# sch_Power.net
KiCad netlist of a schematic drawn in Altium Designer
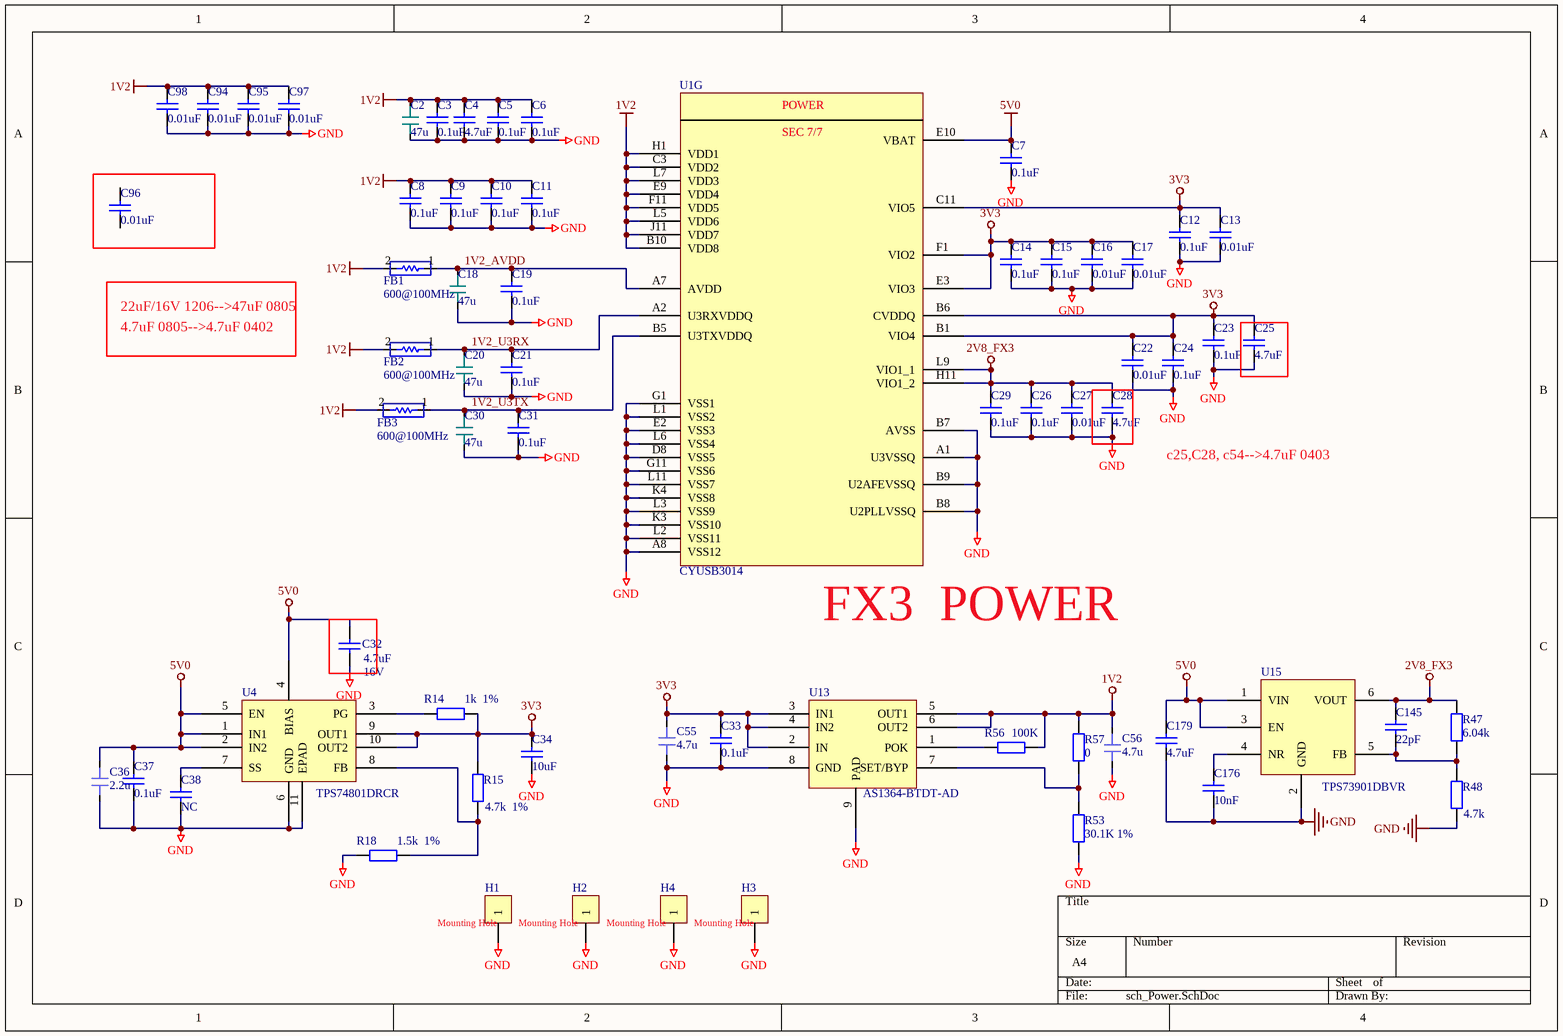
[diagram p0: sch_Power.SchDoc]

(export (version "E")
  (design (tool "Eeschema 10.0.6"))
  (components
    (comp (ref "C2")
      (value "47u")
      (footprint "0805C")
      (description "CC08052B476M5B20D")
      (libsource (lib "V0P1") (part "cap0805"))
    )
    (comp (ref "C3")
      (value "0.1uF")
      (footprint "0402C")
      (description "Capacitor")
      (fields (field (name "PUBLISHER") "Altium Limited"))
      (libsource (lib "Miscellaneous Devices") (part "Cap"))
    )
    (comp (ref "C4")
      (value "4.7uF")
      (footprint "0402C")
      (description "Capacitor")
      (fields (field (name "Comment") "0.1uF") (field (name "PUBLISHER") "Altium Limited"))
      (libsource (lib "Miscellaneous Devices") (part "Cap"))
    )
    (comp (ref "C5")
      (value "0.1uF")
      (footprint "0402C")
      (description "Capacitor")
      (fields (field (name "PUBLISHER") "Altium Limited"))
      (libsource (lib "Miscellaneous Devices") (part "Cap"))
    )
    (comp (ref "C6")
      (value "0.1uF")
      (footprint "0402C")
      (description "Capacitor")
      (fields (field (name "PUBLISHER") "Altium Limited"))
      (libsource (lib "Miscellaneous Devices") (part "Cap"))
    )
    (comp (ref "C7")
      (value "0.1uF")
      (footprint "0402C")
      (description "Capacitor")
      (fields (field (name "PUBLISHER") "Altium Limited"))
      (libsource (lib "Miscellaneous Devices") (part "Cap"))
    )
    (comp (ref "C8")
      (value "0.1uF")
      (footprint "0402C")
      (description "Capacitor")
      (fields (field (name "PUBLISHER") "Altium Limited"))
      (libsource (lib "Miscellaneous Devices") (part "Cap"))
    )
    (comp (ref "C9")
      (value "0.1uF")
      (footprint "0402C")
      (description "Capacitor")
      (fields (field (name "PUBLISHER") "Altium Limited"))
      (libsource (lib "Miscellaneous Devices") (part "Cap"))
    )
    (comp (ref "C10")
      (value "0.1uF")
      (footprint "0402C")
      (description "Capacitor")
      (fields (field (name "PUBLISHER") "Altium Limited"))
      (libsource (lib "Miscellaneous Devices") (part "Cap"))
    )
    (comp (ref "C11")
      (value "0.1uF")
      (footprint "0402C")
      (description "Capacitor")
      (fields (field (name "PUBLISHER") "Altium Limited"))
      (libsource (lib "Miscellaneous Devices") (part "Cap"))
    )
    (comp (ref "C12")
      (value "0.1uF")
      (footprint "0402C")
      (description "Capacitor")
      (fields (field (name "PUBLISHER") "Altium Limited"))
      (libsource (lib "Miscellaneous Devices") (part "Cap"))
    )
    (comp (ref "C13")
      (value "0.01uF")
      (footprint "0402C")
      (description "Capacitor")
      (fields (field (name "PUBLISHER") "Altium Limited"))
      (libsource (lib "Miscellaneous Devices") (part "Cap"))
    )
    (comp (ref "C14")
      (value "0.1uF")
      (footprint "0402C")
      (description "Capacitor")
      (fields (field (name "PUBLISHER") "Altium Limited"))
      (libsource (lib "Miscellaneous Devices") (part "Cap"))
    )
    (comp (ref "C15")
      (value "0.1uF")
      (footprint "0402C")
      (description "Capacitor")
      (fields (field (name "PUBLISHER") "Altium Limited"))
      (libsource (lib "Miscellaneous Devices") (part "Cap"))
    )
    (comp (ref "C16")
      (value "0.01uF")
      (footprint "0402C")
      (description "Capacitor")
      (fields (field (name "PUBLISHER") "Altium Limited"))
      (libsource (lib "Miscellaneous Devices") (part "Cap"))
    )
    (comp (ref "C17")
      (value "0.01uF")
      (footprint "0402C")
      (description "Capacitor")
      (fields (field (name "PUBLISHER") "Altium Limited"))
      (libsource (lib "Miscellaneous Devices") (part "Cap"))
    )
    (comp (ref "C18")
      (value "47u")
      (footprint "0805C")
      (description "CC08052B476M5B20D")
      (libsource (lib "V0P1") (part "cap0805"))
    )
    (comp (ref "C19")
      (value "0.1uF")
      (footprint "0402C")
      (description "Capacitor")
      (fields (field (name "PUBLISHER") "Altium Limited"))
      (libsource (lib "Miscellaneous Devices") (part "Cap"))
    )
    (comp (ref "C20")
      (value "47u")
      (footprint "0805C")
      (description "CC08052B476M5B20D")
      (libsource (lib "V0P1") (part "cap0805"))
    )
    (comp (ref "C21")
      (value "0.1uF")
      (footprint "0402C")
      (description "Capacitor")
      (fields (field (name "PUBLISHER") "Altium Limited"))
      (libsource (lib "Miscellaneous Devices") (part "Cap"))
    )
    (comp (ref "C22")
      (value "0.01uF")
      (footprint "0402C")
      (description "Capacitor")
      (fields (field (name "PUBLISHER") "Altium Limited"))
      (libsource (lib "Miscellaneous Devices") (part "Cap"))
    )
    (comp (ref "C23")
      (value "0.1uF")
      (footprint "0402C")
      (description "Capacitor")
      (fields (field (name "PUBLISHER") "Altium Limited"))
      (libsource (lib "Miscellaneous Devices") (part "Cap"))
    )
    (comp (ref "C24")
      (value "0.1uF")
      (footprint "0402C")
      (description "Capacitor")
      (fields (field (name "PUBLISHER") "Altium Limited"))
      (libsource (lib "Miscellaneous Devices") (part "Cap"))
    )
    (comp (ref "C25")
      (value "4.7uF")
      (footprint "0402C")
      (description "Capacitor")
      (fields (field (name "PUBLISHER") "Altium Limited"))
      (libsource (lib "Miscellaneous Devices") (part "Cap"))
    )
    (comp (ref "C26")
      (value "0.1uF")
      (footprint "0402C")
      (description "Capacitor")
      (fields (field (name "PUBLISHER") "Altium Limited"))
      (libsource (lib "Miscellaneous Devices") (part "Cap"))
    )
    (comp (ref "C27")
      (value "0.01uF")
      (footprint "0402C")
      (description "Capacitor")
      (fields (field (name "PUBLISHER") "Altium Limited"))
      (libsource (lib "Miscellaneous Devices") (part "Cap"))
    )
    (comp (ref "C28")
      (value "4.7uF")
      (footprint "0402C")
      (description "Capacitor")
      (fields (field (name "PUBLISHER") "Altium Limited"))
      (libsource (lib "Miscellaneous Devices") (part "Cap"))
    )
    (comp (ref "C29")
      (value "0.1uF")
      (footprint "0402C")
      (description "Capacitor")
      (fields (field (name "PUBLISHER") "Altium Limited"))
      (libsource (lib "Miscellaneous Devices") (part "Cap"))
    )
    (comp (ref "C30")
      (value "47u")
      (footprint "0805C")
      (description "CC08052B476M5B20D")
      (libsource (lib "V0P1") (part "cap0805"))
    )
    (comp (ref "C31")
      (value "0.1uF")
      (footprint "0402C")
      (description "Capacitor")
      (fields (field (name "PUBLISHER") "Altium Limited"))
      (libsource (lib "Miscellaneous Devices") (part "Cap"))
    )
    (comp (ref "C32")
      (value "4.7uF")
      (footprint "0402C")
      (description "Capacitor")
      (fields (field (name "ALTIUM_VALUE") "16V") (field (name "PUBLISHER") "Altium Limited"))
      (libsource (lib "Miscellaneous Devices") (part "Cap"))
    )
    (comp (ref "C33")
      (value "0.1uF")
      (footprint "0402C")
      (description "Capacitor")
      (fields (field (name "PUBLISHER") "Altium Limited"))
      (libsource (lib "Miscellaneous Devices") (part "Cap"))
    )
    (comp (ref "C34")
      (value "10uF")
      (footprint "0805C")
      (description "Capacitor")
      (fields (field (name "PUBLISHER") "Altium Limited"))
      (libsource (lib "Miscellaneous Devices") (part "Cap"))
    )
    (comp (ref "C36")
      (value "2.2u")
      (footprint "0402C")
      (description "CC0402MRX5R5BB475")
      (libsource (lib "V0P1") (part "cap0402"))
    )
    (comp (ref "C37")
      (value "0.1uF")
      (footprint "0402C")
      (description "Capacitor")
      (fields (field (name "PUBLISHER") "Altium Limited"))
      (libsource (lib "Miscellaneous Devices") (part "Cap"))
    )
    (comp (ref "C38")
      (value "NC")
      (footprint "0402C")
      (description "Capacitor")
      (fields (field (name "PUBLISHER") "Altium Limited"))
      (libsource (lib "Miscellaneous Devices") (part "Cap"))
    )
    (comp (ref "C55")
      (value "4.7u")
      (footprint "0402C")
      (description "CC0402MRX5R5BB475")
      (libsource (lib "V0P1") (part "cap0402"))
    )
    (comp (ref "C56")
      (value "4.7u")
      (footprint "0402C")
      (description "CC0402MRX5R5BB475")
      (libsource (lib "V0P1") (part "cap0402"))
    )
    (comp (ref "C94")
      (value "0.01uF")
      (footprint "0402C")
      (description "Capacitor")
      (fields (field (name "PUBLISHER") "Altium Limited"))
      (libsource (lib "Miscellaneous Devices") (part "Cap"))
    )
    (comp (ref "C95")
      (value "0.01uF")
      (footprint "0402C")
      (description "Capacitor")
      (fields (field (name "PUBLISHER") "Altium Limited"))
      (libsource (lib "Miscellaneous Devices") (part "Cap"))
    )
    (comp (ref "C96")
      (value "0.01uF")
      (footprint "0402C")
      (description "Capacitor")
      (fields (field (name "PUBLISHER") "Altium Limited"))
      (libsource (lib "Miscellaneous Devices") (part "Cap"))
    )
    (comp (ref "C97")
      (value "0.01uF")
      (footprint "0402C")
      (description "Capacitor")
      (fields (field (name "PUBLISHER") "Altium Limited"))
      (libsource (lib "Miscellaneous Devices") (part "Cap"))
    )
    (comp (ref "C98")
      (value "0.01uF")
      (footprint "0402C")
      (description "Capacitor")
      (fields (field (name "PUBLISHER") "Altium Limited"))
      (libsource (lib "Miscellaneous Devices") (part "Cap"))
    )
    (comp (ref "C145")
      (value "22pF")
      (footprint "0805C")
      (description "Capacitor")
      (fields (field (name "PUBLISHER") "Altium Limited"))
      (libsource (lib "Miscellaneous Devices") (part "Cap"))
    )
    (comp (ref "C176")
      (value "10nF")
      (footprint "0402C_L")
      (description "Capacitor")
      (fields (field (name "PUBLISHER") "Altium Limited"))
      (libsource (lib "Miscellaneous Devices") (part "Cap"))
    )
    (comp (ref "C179")
      (value "4.7uF")
      (footprint "0402C_L")
      (description "Capacitor")
      (fields (field (name "PUBLISHER") "Altium Limited"))
      (libsource (lib "Miscellaneous Devices") (part "Cap"))
    )
    (comp (ref "FB1") (value "600@100MHz") (footprint "0603R") (libsource (lib "TXW") (part "600@100MHz")))
    (comp (ref "FB2") (value "600@100MHz") (footprint "0603R") (libsource (lib "TXW") (part "600@100MHz")))
    (comp (ref "FB3") (value "600@100MHz") (footprint "0603R") (libsource (lib "TXW") (part "600@100MHz")))
    (comp (ref "H1")
      (value "CON1")
      (footprint "PAD_M3_D350_450")
      (description "Connector")
      (libsource (lib "SuperSchLib") (part "CON1"))
    )
    (comp (ref "H2")
      (value "CON1")
      (footprint "PAD_M3_D350_450")
      (description "Connector")
      (libsource (lib "SuperSchLib") (part "CON1"))
    )
    (comp (ref "H3")
      (value "CON1")
      (footprint "PAD_M3_D350_450")
      (description "Connector")
      (libsource (lib "SuperSchLib") (part "CON1"))
    )
    (comp (ref "H4")
      (value "CON1")
      (footprint "PAD_M3_D350_450")
      (description "Connector")
      (libsource (lib "SuperSchLib") (part "CON1"))
    )
    (comp (ref "R14")
      (value "1k  1%")
      (footprint "0402R")
      (description "Resistor")
      (fields (field (name "Comment") "1K") (field (name "PUBLISHER") "Altium Limited"))
      (libsource (lib "") (part "Resistor_2"))
    )
    (comp (ref "R15")
      (value "4.7k  1%")
      (footprint "0402R")
      (description "Resistor")
      (fields (field (name "Comment") "4.7K") (field (name "PUBLISHER") "Altium Limited"))
      (libsource (lib "SZG") (part "Resistor"))
    )
    (comp (ref "R18")
      (value "1.5k  1%")
      (footprint "0402R")
      (description "Resistor")
      (fields (field (name "Comment") "1.5K") (field (name "PUBLISHER") "Altium Limited"))
      (libsource (lib "") (part "Resistor_2"))
    )
    (comp (ref "R47")
      (value "6.04k")
      (footprint "0402R")
      (description "Resistor")
      (fields (field (name "Comment") "6.04K") (field (name "PUBLISHER") "Altium Limited"))
      (libsource (lib "") (part "Resistor_1"))
    )
    (comp (ref "R48")
      (value "4.7k")
      (footprint "0402R")
      (description "Resistor")
      (fields (field (name "Comment") "4.7K") (field (name "PUBLISHER") "Altium Limited"))
      (libsource (lib "SZG") (part "Resistor"))
    )
    (comp (ref "R53")
      (value "30.1K 1%")
      (footprint "0402R")
      (description "Resistor")
      (fields (field (name "Comment") "30.1K") (field (name "PUBLISHER") "Altium Limited"))
      (libsource (lib "SZG") (part "Resistor"))
    )
    (comp (ref "R56")
      (value "100K")
      (footprint "0402R")
      (description "Resistor")
      (fields (field (name "PUBLISHER") "Altium Limited"))
      (libsource (lib "") (part "Resistor_2"))
    )
    (comp (ref "R57")
      (value "0")
      (footprint "0402R")
      (description "Resistor")
      (fields (field (name "Comment") "0R") (field (name "PUBLISHER") "Altium Limited"))
      (libsource (lib "SZG") (part "Resistor"))
    )
    (comp (ref "U1")
      (value "CYUSB3014")
      (footprint "FBGA121_P80L100W100H11")
      (libsource (lib "TXW") (part "CYUSB3014"))
    )
    (comp (ref "U4")
      (value "TPS74801DRCR")
      (footprint "SON10_P50L32W32H10_DRC")
      (libsource (lib "TXW") (part "TPS74801DRCR"))
    )
    (comp (ref "U13")
      (value "AS1364-BTDT-AD")
      (footprint "TDFN8_P65L30W30H08")
      (libsource (lib "TXW") (part "AS1364-BTDT-AD"))
    )
    (comp (ref "U15") (value "TPS73901DBVR") (libsource (lib "SZG") (part "TPS73901DBVR")))
  )
  (nets
    (net (code "1") (name "/1V2_AVDD") (class "Default")
      (node (ref "C18") (pin "1") (pinfunction "1_1") (pintype "passive"))
      (node (ref "C19") (pin "2") (pinfunction "2_2") (pintype "passive"))
      (node (ref "FB1") (pin "1") (pinfunction "1_1") (pintype "passive"))
      (node (ref "U1") (pin "A7") (pinfunction "AVDD_A7") (pintype "passive"))
    )
    (net (code "2") (name "/1V2_U3RX") (class "Default")
      (node (ref "C20") (pin "1") (pinfunction "1_1") (pintype "passive"))
      (node (ref "C21") (pin "2") (pinfunction "2_2") (pintype "passive"))
      (node (ref "FB2") (pin "1") (pinfunction "1_1") (pintype "passive"))
      (node (ref "U1") (pin "A2") (pinfunction "U3RXVDDQ_A2") (pintype "passive"))
    )
    (net (code "3") (name "/1V2_U3TX") (class "Default")
      (node (ref "C30") (pin "1") (pinfunction "1_1") (pintype "passive"))
      (node (ref "C31") (pin "2") (pinfunction "2_2") (pintype "passive"))
      (node (ref "FB3") (pin "1") (pinfunction "1_1") (pintype "passive"))
      (node (ref "U1") (pin "B5") (pinfunction "U3TXVDDQ_B5") (pintype "passive"))
    )
    (net (code "4") (name "1V2") (class "Default")
      (node (ref "C10") (pin "2") (pinfunction "2_2") (pintype "passive"))
      (node (ref "C11") (pin "2") (pinfunction "2_2") (pintype "passive"))
      (node (ref "C2") (pin "1") (pinfunction "1_1") (pintype "passive"))
      (node (ref "C3") (pin "2") (pinfunction "2_2") (pintype "passive"))
      (node (ref "C4") (pin "2") (pinfunction "2_2") (pintype "passive"))
      (node (ref "C5") (pin "2") (pinfunction "2_2") (pintype "passive"))
      (node (ref "C56") (pin "1") (pinfunction "1_1") (pintype "passive"))
      (node (ref "C6") (pin "2") (pinfunction "2_2") (pintype "passive"))
      (node (ref "C8") (pin "2") (pinfunction "2_2") (pintype "passive"))
      (node (ref "C9") (pin "2") (pinfunction "2_2") (pintype "passive"))
      (node (ref "C94") (pin "2") (pinfunction "2_2") (pintype "passive"))
      (node (ref "C95") (pin "2") (pinfunction "2_2") (pintype "passive"))
      (node (ref "C97") (pin "2") (pinfunction "2_2") (pintype "passive"))
      (node (ref "C98") (pin "2") (pinfunction "2_2") (pintype "passive"))
      (node (ref "FB1") (pin "2") (pinfunction "2_2") (pintype "passive"))
      (node (ref "FB2") (pin "2") (pinfunction "2_2") (pintype "passive"))
      (node (ref "FB3") (pin "2") (pinfunction "2_2") (pintype "passive"))
      (node (ref "R56") (pin "1") (pinfunction "1_1") (pintype "passive"))
      (node (ref "R57") (pin "1") (pinfunction "1_1") (pintype "passive"))
      (node (ref "U1") (pin "B10") (pinfunction "VDD8_B10") (pintype "passive"))
      (node (ref "U1") (pin "C3") (pinfunction "VDD2_C3") (pintype "passive"))
      (node (ref "U1") (pin "E9") (pinfunction "VDD4_E9") (pintype "passive"))
      (node (ref "U1") (pin "F11") (pinfunction "VDD5_F11") (pintype "passive"))
      (node (ref "U1") (pin "H1") (pinfunction "VDD1_H1") (pintype "passive"))
      (node (ref "U1") (pin "J11") (pinfunction "VDD7_J11") (pintype "passive"))
      (node (ref "U1") (pin "L5") (pinfunction "VDD6_L5") (pintype "passive"))
      (node (ref "U1") (pin "L7") (pinfunction "VDD3_L7") (pintype "passive"))
      (node (ref "U13") (pin "5") (pinfunction "OUT1_5") (pintype "passive"))
      (node (ref "U13") (pin "6") (pinfunction "OUT2_6") (pintype "passive"))
    )
    (net (code "5") (name "2V8_FX3") (class "Default")
      (node (ref "C145") (pin "2") (pinfunction "2_2") (pintype "passive"))
      (node (ref "C26") (pin "2") (pinfunction "2_2") (pintype "passive"))
      (node (ref "C27") (pin "2") (pinfunction "2_2") (pintype "passive"))
      (node (ref "C28") (pin "2") (pinfunction "2_2") (pintype "passive"))
      (node (ref "C29") (pin "2") (pinfunction "2_2") (pintype "passive"))
      (node (ref "R47") (pin "2") (pinfunction "2_2") (pintype "passive"))
      (node (ref "U1") (pin "H11") (pinfunction "VIO1_2_H11") (pintype "passive"))
      (node (ref "U1") (pin "L9") (pinfunction "VIO1_1_L9") (pintype "passive"))
      (node (ref "U15") (pin "6") (pinfunction "VOUT_6") (pintype "passive"))
    )
    (net (code "6") (name "3V3") (class "Default")
      (node (ref "C12") (pin "2") (pinfunction "2_2") (pintype "passive"))
      (node (ref "C13") (pin "2") (pinfunction "2_2") (pintype "passive"))
      (node (ref "C14") (pin "2") (pinfunction "2_2") (pintype "passive"))
      (node (ref "C15") (pin "2") (pinfunction "2_2") (pintype "passive"))
      (node (ref "C16") (pin "2") (pinfunction "2_2") (pintype "passive"))
      (node (ref "C17") (pin "2") (pinfunction "2_2") (pintype "passive"))
      (node (ref "C22") (pin "2") (pinfunction "2_2") (pintype "passive"))
      (node (ref "C23") (pin "2") (pinfunction "2_2") (pintype "passive"))
      (node (ref "C24") (pin "2") (pinfunction "2_2") (pintype "passive"))
      (node (ref "C25") (pin "2") (pinfunction "2_2") (pintype "passive"))
      (node (ref "C33") (pin "2") (pinfunction "2_2") (pintype "passive"))
      (node (ref "C34") (pin "2") (pinfunction "2_2") (pintype "passive"))
      (node (ref "C55") (pin "1") (pinfunction "1_1") (pintype "passive"))
      (node (ref "R14") (pin "1") (pinfunction "1_1") (pintype "passive"))
      (node (ref "R15") (pin "1") (pinfunction "1_1") (pintype "passive"))
      (node (ref "U1") (pin "B1") (pinfunction "VIO4_B1") (pintype "passive"))
      (node (ref "U1") (pin "B6") (pinfunction "CVDDQ_B6") (pintype "passive"))
      (node (ref "U1") (pin "C11") (pinfunction "VIO5_C11") (pintype "power_in"))
      (node (ref "U1") (pin "E3") (pinfunction "VIO3_E3") (pintype "passive"))
      (node (ref "U1") (pin "F1") (pinfunction "VIO2_F1") (pintype "passive"))
      (node (ref "U13") (pin "2") (pinfunction "IN_2") (pintype "passive"))
      (node (ref "U13") (pin "3") (pinfunction "IN1_3") (pintype "passive"))
      (node (ref "U13") (pin "4") (pinfunction "IN2_4") (pintype "passive"))
      (node (ref "U4") (pin "10") (pinfunction "OUT2_10") (pintype "passive"))
      (node (ref "U4") (pin "9") (pinfunction "OUT1_9") (pintype "passive"))
    )
    (net (code "7") (name "5V0") (class "Default")
      (node (ref "C179") (pin "2") (pinfunction "2_2") (pintype "passive"))
      (node (ref "C32") (pin "1") (pinfunction "1_1") (pintype "passive"))
      (node (ref "C36") (pin "1") (pinfunction "1_1") (pintype "passive"))
      (node (ref "C37") (pin "2") (pinfunction "2_2") (pintype "passive"))
      (node (ref "C7") (pin "2") (pinfunction "2_2") (pintype "passive"))
      (node (ref "U1") (pin "E10") (pinfunction "VBAT_E10") (pintype "passive"))
      (node (ref "U15") (pin "1") (pinfunction "VIN_1") (pintype "passive"))
      (node (ref "U15") (pin "3") (pinfunction "EN_3") (pintype "passive"))
      (node (ref "U4") (pin "1") (pinfunction "IN1_1") (pintype "passive"))
      (node (ref "U4") (pin "2") (pinfunction "IN2_2") (pintype "passive"))
      (node (ref "U4") (pin "4") (pinfunction "BIAS_4") (pintype "passive"))
      (node (ref "U4") (pin "5") (pinfunction "EN_5") (pintype "passive"))
    )
    (net (code "8") (name "GND") (class "Default")
      (node (ref "C10") (pin "1") (pinfunction "1_1") (pintype "passive"))
      (node (ref "C11") (pin "1") (pinfunction "1_1") (pintype "passive"))
      (node (ref "C12") (pin "1") (pinfunction "1_1") (pintype "passive"))
      (node (ref "C13") (pin "1") (pinfunction "1_1") (pintype "passive"))
      (node (ref "C14") (pin "1") (pinfunction "1_1") (pintype "passive"))
      (node (ref "C15") (pin "1") (pinfunction "1_1") (pintype "passive"))
      (node (ref "C16") (pin "1") (pinfunction "1_1") (pintype "passive"))
      (node (ref "C17") (pin "1") (pinfunction "1_1") (pintype "passive"))
      (node (ref "C176") (pin "1") (pinfunction "1_1") (pintype "passive"))
      (node (ref "C179") (pin "1") (pinfunction "1_1") (pintype "passive"))
      (node (ref "C18") (pin "2") (pinfunction "2_2") (pintype "passive"))
      (node (ref "C19") (pin "1") (pinfunction "1_1") (pintype "passive"))
      (node (ref "C2") (pin "2") (pinfunction "2_2") (pintype "passive"))
      (node (ref "C20") (pin "2") (pinfunction "2_2") (pintype "passive"))
      (node (ref "C21") (pin "1") (pinfunction "1_1") (pintype "passive"))
      (node (ref "C22") (pin "1") (pinfunction "1_1") (pintype "passive"))
      (node (ref "C23") (pin "1") (pinfunction "1_1") (pintype "passive"))
      (node (ref "C24") (pin "1") (pinfunction "1_1") (pintype "passive"))
      (node (ref "C25") (pin "1") (pinfunction "1_1") (pintype "passive"))
      (node (ref "C26") (pin "1") (pinfunction "1_1") (pintype "passive"))
      (node (ref "C27") (pin "1") (pinfunction "1_1") (pintype "passive"))
      (node (ref "C28") (pin "1") (pinfunction "1_1") (pintype "passive"))
      (node (ref "C29") (pin "1") (pinfunction "1_1") (pintype "passive"))
      (node (ref "C3") (pin "1") (pinfunction "1_1") (pintype "passive"))
      (node (ref "C30") (pin "2") (pinfunction "2_2") (pintype "passive"))
      (node (ref "C31") (pin "1") (pinfunction "1_1") (pintype "passive"))
      (node (ref "C32") (pin "2") (pinfunction "2_2") (pintype "passive"))
      (node (ref "C33") (pin "1") (pinfunction "1_1") (pintype "passive"))
      (node (ref "C34") (pin "1") (pinfunction "1_1") (pintype "passive"))
      (node (ref "C36") (pin "2") (pinfunction "2_2") (pintype "passive"))
      (node (ref "C37") (pin "1") (pinfunction "1_1") (pintype "passive"))
      (node (ref "C38") (pin "1") (pinfunction "1_1") (pintype "passive"))
      (node (ref "C4") (pin "1") (pinfunction "1_1") (pintype "passive"))
      (node (ref "C5") (pin "1") (pinfunction "1_1") (pintype "passive"))
      (node (ref "C55") (pin "2") (pinfunction "2_2") (pintype "passive"))
      (node (ref "C56") (pin "2") (pinfunction "2_2") (pintype "passive"))
      (node (ref "C6") (pin "1") (pinfunction "1_1") (pintype "passive"))
      (node (ref "C7") (pin "1") (pinfunction "1_1") (pintype "passive"))
      (node (ref "C8") (pin "1") (pinfunction "1_1") (pintype "passive"))
      (node (ref "C9") (pin "1") (pinfunction "1_1") (pintype "passive"))
      (node (ref "C94") (pin "1") (pinfunction "1_1") (pintype "passive"))
      (node (ref "C95") (pin "1") (pinfunction "1_1") (pintype "passive"))
      (node (ref "C97") (pin "1") (pinfunction "1_1") (pintype "passive"))
      (node (ref "C98") (pin "1") (pinfunction "1_1") (pintype "passive"))
      (node (ref "H1") (pin "1") (pinfunction "1_1") (pintype "passive"))
      (node (ref "H2") (pin "1") (pinfunction "1_1") (pintype "passive"))
      (node (ref "H3") (pin "1") (pinfunction "1_1") (pintype "passive"))
      (node (ref "H4") (pin "1") (pinfunction "1_1") (pintype "passive"))
      (node (ref "R18") (pin "2") (pinfunction "2_2") (pintype "passive"))
      (node (ref "R48") (pin "2") (pinfunction "2_2") (pintype "passive"))
      (node (ref "R53") (pin "2") (pinfunction "2_2") (pintype "passive"))
      (node (ref "U1") (pin "A1") (pinfunction "U3VSSQ_A1") (pintype "passive"))
      (node (ref "U1") (pin "A8") (pinfunction "VSS12_A8") (pintype "passive"))
      (node (ref "U1") (pin "B7") (pinfunction "AVSS_B7") (pintype "passive"))
      (node (ref "U1") (pin "B8") (pinfunction "U2PLLVSSQ_B8") (pintype "passive"))
      (node (ref "U1") (pin "B9") (pinfunction "U2AFEVSSQ_B9") (pintype "passive"))
      (node (ref "U1") (pin "D8") (pinfunction "VSS5_D8") (pintype "passive"))
      (node (ref "U1") (pin "E2") (pinfunction "VSS3_E2") (pintype "passive"))
      (node (ref "U1") (pin "G1") (pinfunction "VSS1_G1") (pintype "passive"))
      (node (ref "U1") (pin "G11") (pinfunction "VSS6_G11") (pintype "passive"))
      (node (ref "U1") (pin "K3") (pinfunction "VSS10_K3") (pintype "passive"))
      (node (ref "U1") (pin "K4") (pinfunction "VSS8_K4") (pintype "passive"))
      (node (ref "U1") (pin "L1") (pinfunction "VSS2_L1") (pintype "passive"))
      (node (ref "U1") (pin "L11") (pinfunction "VSS7_L11") (pintype "passive"))
      (node (ref "U1") (pin "L2") (pinfunction "VSS11_L2") (pintype "passive"))
      (node (ref "U1") (pin "L3") (pinfunction "VSS9_L3") (pintype "passive"))
      (node (ref "U1") (pin "L6") (pinfunction "VSS4_L6") (pintype "passive"))
      (node (ref "U13") (pin "8") (pinfunction "GND_8") (pintype "passive"))
      (node (ref "U13") (pin "9") (pinfunction "PAD_9") (pintype "passive"))
      (node (ref "U15") (pin "2") (pinfunction "GND_2") (pintype "passive"))
      (node (ref "U4") (pin "11") (pinfunction "EPAD_11") (pintype "passive"))
      (node (ref "U4") (pin "6") (pinfunction "GND_6") (pintype "passive"))
    )
    (net (code "9") (name "Net-(U4-FB)") (class "Default")
      (node (ref "R15") (pin "2") (pinfunction "2_2") (pintype "passive"))
      (node (ref "R18") (pin "1") (pinfunction "1_1") (pintype "passive"))
      (node (ref "U4") (pin "8") (pinfunction "FB_8") (pintype "passive"))
    )
    (net (code "10") (name "Net-(U4-PG)") (class "Default")
      (node (ref "R14") (pin "2") (pinfunction "2_2") (pintype "passive"))
      (node (ref "U4") (pin "3") (pinfunction "PG_3") (pintype "passive"))
    )
    (net (code "11") (name "Net-(U4-SS)") (class "Default")
      (node (ref "C38") (pin "2") (pinfunction "2_2") (pintype "passive"))
      (node (ref "U4") (pin "7") (pinfunction "SS_7") (pintype "passive"))
    )
    (net (code "12") (name "Net-(U13-POK)") (class "Default")
      (node (ref "R56") (pin "2") (pinfunction "2_2") (pintype "passive"))
      (node (ref "U13") (pin "1") (pinfunction "POK_1") (pintype "passive"))
    )
    (net (code "13") (name "Net-(U13-SET{slash}BYP)") (class "Default")
      (node (ref "R53") (pin "1") (pinfunction "1_1") (pintype "passive"))
      (node (ref "R57") (pin "2") (pinfunction "2_2") (pintype "passive"))
      (node (ref "U13") (pin "7") (pinfunction "SET/BYP_7") (pintype "passive"))
    )
    (net (code "14") (name "Net-(U15-FB)") (class "Default")
      (node (ref "C145") (pin "1") (pinfunction "1_1") (pintype "passive"))
      (node (ref "R47") (pin "1") (pinfunction "1_1") (pintype "passive"))
      (node (ref "R48") (pin "1") (pinfunction "1_1") (pintype "passive"))
      (node (ref "U15") (pin "5") (pinfunction "FB_5") (pintype "passive"))
    )
    (net (code "15") (name "Net-(U15-NR)") (class "Default")
      (node (ref "C176") (pin "2") (pinfunction "2_2") (pintype "passive"))
      (node (ref "U15") (pin "4") (pinfunction "NR_4") (pintype "passive"))
    )
    (net (code "16") (name "unconnected-(C96-Pad1)") (class "Default")
      (node (ref "C96") (pin "1") (pinfunction "1_1") (pintype "passive"))
    )
    (net (code "17") (name "unconnected-(C96-Pad2)") (class "Default")
      (node (ref "C96") (pin "2") (pinfunction "2_2") (pintype "passive"))
    )
  )
)
